# whare_hauora_sensor_r1.net
KiCad netlist of a schematic drawn in EAGLE
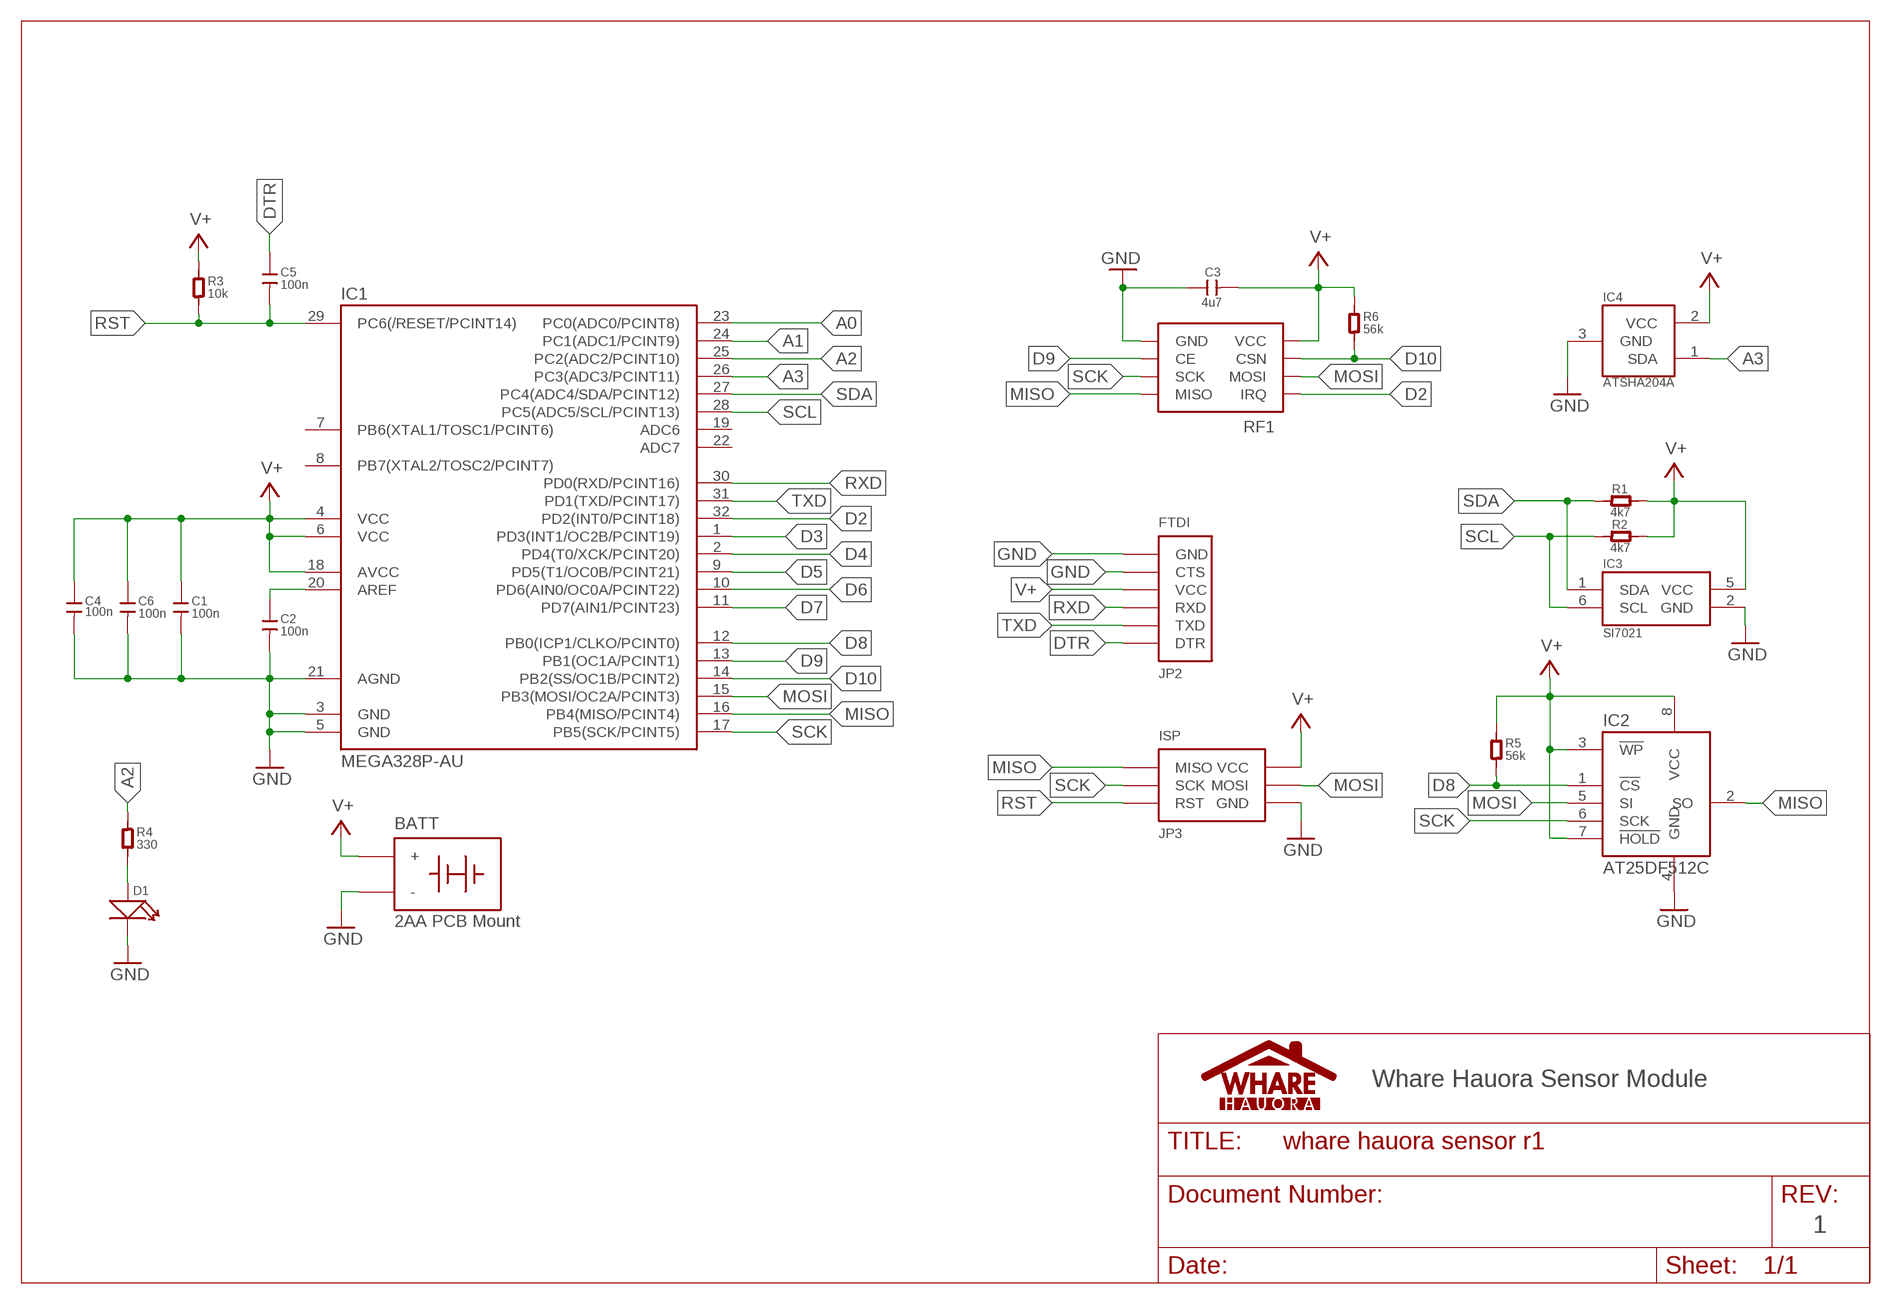
[diagram p0: schematic, sheet 1]

(export (version "E")
  (design (tool "Eeschema 10.0.6"))
  (components
    (comp (ref "BATT")
      (value "2AA-PACK")
      (footprint "eagle-import:2AA-PACK_")
      (libsource (lib "eagle-import") (part "2AA-PACK"))
    )
    (comp (ref "C1")
      (value "100n")
      (footprint "eagle-import:C0603")
      (libsource (lib "eagle-import") (part "CAP-0603"))
    )
    (comp (ref "C2")
      (value "100n")
      (footprint "eagle-import:C0603")
      (libsource (lib "eagle-import") (part "CAP-0603"))
    )
    (comp (ref "C3")
      (value "4u7")
      (footprint "eagle-import:C0603")
      (libsource (lib "eagle-import") (part "CAP-0603"))
    )
    (comp (ref "C4")
      (value "100n")
      (footprint "eagle-import:C0603")
      (libsource (lib "eagle-import") (part "CAP-0603"))
    )
    (comp (ref "C5")
      (value "100n")
      (footprint "eagle-import:C0603")
      (libsource (lib "eagle-import") (part "CAP-0603"))
    )
    (comp (ref "C6")
      (value "100n")
      (footprint "eagle-import:C0603")
      (libsource (lib "eagle-import") (part "CAP-0603"))
    )
    (comp (ref "D1")
      (value "LED-0603")
      (footprint "eagle-import:LED-0603")
      (libsource (lib "eagle-import") (part "LED-0603"))
    )
    (comp (ref "IC1")
      (value "MEGA328P-AU")
      (footprint "eagle-import:TQFP32-08")
      (libsource (lib "eagle-import") (part "MEGA48/88/168-AU"))
    )
    (comp (ref "IC2")
      (value "AT25DF512C")
      (footprint "eagle-import:SO8")
      (libsource (lib "eagle-import") (part "AT25DF512C"))
    )
    (comp (ref "IC3")
      (value "SI7021")
      (footprint "eagle-import:DFN6")
      (libsource (lib "eagle-import") (part "SI7021"))
    )
    (comp (ref "IC4")
      (value "ATSHA204A")
      (footprint "eagle-import:SOT23")
      (libsource (lib "eagle-import") (part "ATSHA204A"))
    )
    (comp (ref "JP2")
      (value "FTDI")
      (footprint "eagle-import:FTDI")
      (libsource (lib "eagle-import") (part "FTDI"))
    )
    (comp (ref "JP3")
      (value "ISP")
      (footprint "eagle-import:ISP")
      (libsource (lib "eagle-import") (part "ISP"))
    )
    (comp (ref "R1")
      (value "4k7")
      (footprint "eagle-import:R0603")
      (libsource (lib "eagle-import") (part "R-0603"))
    )
    (comp (ref "R2")
      (value "4k7")
      (footprint "eagle-import:R0603")
      (libsource (lib "eagle-import") (part "R-0603"))
    )
    (comp (ref "R3")
      (value "10k")
      (footprint "eagle-import:R0603")
      (libsource (lib "eagle-import") (part "R-0603"))
    )
    (comp (ref "R4")
      (value "330")
      (footprint "eagle-import:R0603")
      (libsource (lib "eagle-import") (part "R-0603"))
    )
    (comp (ref "R5")
      (value "56k")
      (footprint "eagle-import:R0603")
      (libsource (lib "eagle-import") (part "R-0603"))
    )
    (comp (ref "R6")
      (value "56k")
      (footprint "eagle-import:R0603")
      (libsource (lib "eagle-import") (part "R-0603"))
    )
    (comp (ref "RF1")
      (value "NRF24L01+")
      (footprint "eagle-import:NRF24L01+")
      (libsource (lib "eagle-import") (part "NRF24L01+"))
    )
  )
  (nets
    (net (code "1") (name "A0") (class "Default")
      (node (ref "IC1") (pin "23") (pinfunction "PC0(ADC0/PCINT8)_23") (pintype "bidirectional"))
    )
    (net (code "2") (name "A1") (class "Default")
      (node (ref "IC1") (pin "24") (pinfunction "PC1(ADC1/PCINT9)_24") (pintype "bidirectional"))
    )
    (net (code "3") (name "A2") (class "Default")
      (node (ref "IC1") (pin "25") (pinfunction "PC2(ADC2/PCINT10)_25") (pintype "bidirectional"))
      (node (ref "R4") (pin "1") (pinfunction "1_1") (pintype "bidirectional"))
    )
    (net (code "4") (name "A3") (class "Default")
      (node (ref "IC1") (pin "26") (pinfunction "PC3(ADC3/PCINT11)_26") (pintype "bidirectional"))
      (node (ref "IC4") (pin "1") (pinfunction "SDA_1") (pintype "bidirectional"))
    )
    (net (code "5") (name "D2") (class "Default")
      (node (ref "IC1") (pin "32") (pinfunction "PD2(INT0/PCINT18)_32") (pintype "bidirectional"))
      (node (ref "RF1") (pin "P$8") (pinfunction "IRQ_P$8") (pintype "bidirectional"))
    )
    (net (code "6") (name "D3") (class "Default")
      (node (ref "IC1") (pin "1") (pinfunction "PD3(INT1/OC2B/PCINT19)_1") (pintype "bidirectional"))
    )
    (net (code "7") (name "D4") (class "Default")
      (node (ref "IC1") (pin "2") (pinfunction "PD4(T0/XCK/PCINT20)_2") (pintype "bidirectional"))
    )
    (net (code "8") (name "D5") (class "Default")
      (node (ref "IC1") (pin "9") (pinfunction "PD5(T1/OC0B/PCINT21)_9") (pintype "bidirectional"))
    )
    (net (code "9") (name "D6") (class "Default")
      (node (ref "IC1") (pin "10") (pinfunction "PD6(AIN0/OC0A/PCINT22)_10") (pintype "bidirectional"))
    )
    (net (code "10") (name "D7") (class "Default")
      (node (ref "IC1") (pin "11") (pinfunction "PD7(AIN1/PCINT23)_11") (pintype "bidirectional"))
    )
    (net (code "11") (name "D8") (class "Default")
      (node (ref "IC1") (pin "12") (pinfunction "PB0(ICP1/CLKO/PCINT0)_12") (pintype "bidirectional"))
      (node (ref "IC2") (pin "1") (pinfunction "~{CS}_1") (pintype "input"))
      (node (ref "R5") (pin "1") (pinfunction "1_1") (pintype "bidirectional"))
    )
    (net (code "12") (name "D9") (class "Default")
      (node (ref "IC1") (pin "13") (pinfunction "PB1(OC1A/PCINT1)_13") (pintype "bidirectional"))
      (node (ref "RF1") (pin "P$3") (pinfunction "CE_P$3") (pintype "bidirectional"))
    )
    (net (code "13") (name "D10") (class "Default")
      (node (ref "IC1") (pin "14") (pinfunction "PB2(SS/OC1B/PCINT2)_14") (pintype "bidirectional"))
      (node (ref "R6") (pin "1") (pinfunction "1_1") (pintype "bidirectional"))
      (node (ref "RF1") (pin "P$4") (pinfunction "CSN_P$4") (pintype "bidirectional"))
    )
    (net (code "14") (name "DTR") (class "Default")
      (node (ref "C5") (pin "1") (pinfunction "1_1") (pintype "passive"))
      (node (ref "JP2") (pin "DTR") (pinfunction "DTR_DTR") (pintype "bidirectional"))
    )
    (net (code "15") (name "GND") (class "Default")
      (node (ref "BATT") (pin "-") (pinfunction "-_-") (pintype "bidirectional"))
      (node (ref "C1") (pin "2") (pinfunction "2_2") (pintype "passive"))
      (node (ref "C2") (pin "2") (pinfunction "2_2") (pintype "passive"))
      (node (ref "C3") (pin "1") (pinfunction "1_1") (pintype "passive"))
      (node (ref "C4") (pin "2") (pinfunction "2_2") (pintype "passive"))
      (node (ref "C6") (pin "2") (pinfunction "2_2") (pintype "passive"))
      (node (ref "D1") (pin "-") (pinfunction "-_-") (pintype "passive"))
      (node (ref "IC1") (pin "21") (pinfunction "AGND_21") (pintype "power_in"))
      (node (ref "IC1") (pin "3") (pinfunction "GND_3") (pintype "power_in"))
      (node (ref "IC1") (pin "5") (pinfunction "GND_5") (pintype "power_in"))
      (node (ref "IC2") (pin "4") (pinfunction "GND_4") (pintype "power_in"))
      (node (ref "IC3") (pin "2") (pinfunction "GND_2") (pintype "bidirectional"))
      (node (ref "IC4") (pin "3") (pinfunction "GND_3") (pintype "bidirectional"))
      (node (ref "JP2") (pin "CTS") (pinfunction "CTS_CTS") (pintype "bidirectional"))
      (node (ref "JP2") (pin "GND") (pinfunction "GND_GND") (pintype "bidirectional"))
      (node (ref "JP3") (pin "GND") (pinfunction "GND_GND") (pintype "bidirectional"))
      (node (ref "RF1") (pin "P$1") (pinfunction "GND_P$1") (pintype "bidirectional"))
    )
    (net (code "16") (name "MISO") (class "Default")
      (node (ref "IC1") (pin "16") (pinfunction "PB4(MISO/PCINT4)_16") (pintype "bidirectional"))
      (node (ref "IC2") (pin "2") (pinfunction "SO_2") (pintype "output"))
      (node (ref "JP3") (pin "MISO") (pinfunction "MISO_MISO") (pintype "bidirectional"))
      (node (ref "RF1") (pin "P$7") (pinfunction "MISO_P$7") (pintype "bidirectional"))
    )
    (net (code "17") (name "MOSI") (class "Default")
      (node (ref "IC1") (pin "15") (pinfunction "PB3(MOSI/OC2A/PCINT3)_15") (pintype "bidirectional"))
      (node (ref "IC2") (pin "5") (pinfunction "SI_5") (pintype "input"))
      (node (ref "JP3") (pin "MOSI") (pinfunction "MOSI_MOSI") (pintype "bidirectional"))
      (node (ref "RF1") (pin "P$6") (pinfunction "MOSI_P$6") (pintype "bidirectional"))
    )
    (net (code "18") (name "Net-(D1-Pad+)") (class "Default")
      (node (ref "D1") (pin "+") (pinfunction "+_+") (pintype "passive"))
      (node (ref "R4") (pin "2") (pinfunction "2_2") (pintype "bidirectional"))
    )
    (net (code "19") (name "Net-(IC1-AREF)") (class "Default")
      (node (ref "C2") (pin "1") (pinfunction "1_1") (pintype "passive"))
      (node (ref "IC1") (pin "20") (pinfunction "AREF_20") (pintype "passive"))
    )
    (net (code "20") (name "RST") (class "Default")
      (node (ref "C5") (pin "2") (pinfunction "2_2") (pintype "passive"))
      (node (ref "IC1") (pin "29") (pinfunction "PC6(/RESET/PCINT14)_29") (pintype "bidirectional"))
      (node (ref "JP3") (pin "RST") (pinfunction "RST_RST") (pintype "bidirectional"))
      (node (ref "R3") (pin "1") (pinfunction "1_1") (pintype "bidirectional"))
    )
    (net (code "21") (name "RXD") (class "Default")
      (node (ref "IC1") (pin "30") (pinfunction "PD0(RXD/PCINT16)_30") (pintype "bidirectional"))
      (node (ref "JP2") (pin "RXD") (pinfunction "RXD_RXD") (pintype "bidirectional"))
    )
    (net (code "22") (name "SCK") (class "Default")
      (node (ref "IC1") (pin "17") (pinfunction "PB5(SCK/PCINT5)_17") (pintype "bidirectional"))
      (node (ref "IC2") (pin "6") (pinfunction "SCK_6") (pintype "input"))
      (node (ref "JP3") (pin "SCK") (pinfunction "SCK_SCK") (pintype "bidirectional"))
      (node (ref "RF1") (pin "P$5") (pinfunction "SCK_P$5") (pintype "bidirectional"))
    )
    (net (code "23") (name "SCL") (class "Default")
      (node (ref "IC1") (pin "28") (pinfunction "PC5(ADC5/SCL/PCINT13)_28") (pintype "bidirectional"))
      (node (ref "IC3") (pin "6") (pinfunction "SCL_6") (pintype "bidirectional"))
      (node (ref "R2") (pin "1") (pinfunction "1_1") (pintype "bidirectional"))
    )
    (net (code "24") (name "SDA") (class "Default")
      (node (ref "IC1") (pin "27") (pinfunction "PC4(ADC4/SDA/PCINT12)_27") (pintype "bidirectional"))
      (node (ref "IC3") (pin "1") (pinfunction "SDA_1") (pintype "bidirectional"))
      (node (ref "R1") (pin "1") (pinfunction "1_1") (pintype "bidirectional"))
    )
    (net (code "25") (name "TXD") (class "Default")
      (node (ref "IC1") (pin "31") (pinfunction "PD1(TXD/PCINT17)_31") (pintype "bidirectional"))
      (node (ref "JP2") (pin "TXD") (pinfunction "TXD_TXD") (pintype "bidirectional"))
    )
    (net (code "26") (name "V+") (class "Default")
      (node (ref "BATT") (pin "+") (pinfunction "+_+") (pintype "bidirectional"))
      (node (ref "C1") (pin "1") (pinfunction "1_1") (pintype "passive"))
      (node (ref "C3") (pin "2") (pinfunction "2_2") (pintype "passive"))
      (node (ref "C4") (pin "1") (pinfunction "1_1") (pintype "passive"))
      (node (ref "C6") (pin "1") (pinfunction "1_1") (pintype "passive"))
      (node (ref "IC1") (pin "18") (pinfunction "AVCC_18") (pintype "passive"))
      (node (ref "IC1") (pin "4") (pinfunction "VCC_4") (pintype "power_in"))
      (node (ref "IC1") (pin "6") (pinfunction "VCC_6") (pintype "power_in"))
      (node (ref "IC2") (pin "3") (pinfunction "~{WP}_3") (pintype "input"))
      (node (ref "IC2") (pin "7") (pinfunction "~{HOLD}_7") (pintype "input"))
      (node (ref "IC2") (pin "8") (pinfunction "VCC_8") (pintype "bidirectional"))
      (node (ref "IC3") (pin "5") (pinfunction "VCC_5") (pintype "bidirectional"))
      (node (ref "IC4") (pin "2") (pinfunction "VCC_2") (pintype "bidirectional"))
      (node (ref "JP2") (pin "VCC") (pinfunction "VCC_VCC") (pintype "bidirectional"))
      (node (ref "JP3") (pin "VCC") (pinfunction "VCC_VCC") (pintype "bidirectional"))
      (node (ref "R1") (pin "2") (pinfunction "2_2") (pintype "bidirectional"))
      (node (ref "R2") (pin "2") (pinfunction "2_2") (pintype "bidirectional"))
      (node (ref "R3") (pin "2") (pinfunction "2_2") (pintype "bidirectional"))
      (node (ref "R5") (pin "2") (pinfunction "2_2") (pintype "bidirectional"))
      (node (ref "R6") (pin "2") (pinfunction "2_2") (pintype "bidirectional"))
      (node (ref "RF1") (pin "P$2") (pinfunction "VCC_P$2") (pintype "bidirectional"))
    )
    (net (code "27") (name "unconnected-(IC1-ADC6-Pad19)") (class "Default")
      (node (ref "IC1") (pin "19") (pinfunction "ADC6_19") (pintype "passive"))
    )
    (net (code "28") (name "unconnected-(IC1-ADC7-Pad22)") (class "Default")
      (node (ref "IC1") (pin "22") (pinfunction "ADC7_22") (pintype "passive"))
    )
    (net (code "29") (name "unconnected-(IC1-PB6(XTAL1{slash}TOSC1{slash}PCINT6)-Pad7)") (class "Default")
      (node (ref "IC1") (pin "7") (pinfunction "PB6(XTAL1/TOSC1/PCINT6)_7") (pintype "bidirectional"))
    )
    (net (code "30") (name "unconnected-(IC1-PB7(XTAL2{slash}TOSC2{slash}PCINT7)-Pad8)") (class "Default")
      (node (ref "IC1") (pin "8") (pinfunction "PB7(XTAL2/TOSC2/PCINT7)_8") (pintype "bidirectional"))
    )
  )
)
